# 12V_PowerSupply_V01.net
KiCad netlist of a schematic drawn in EAGLE
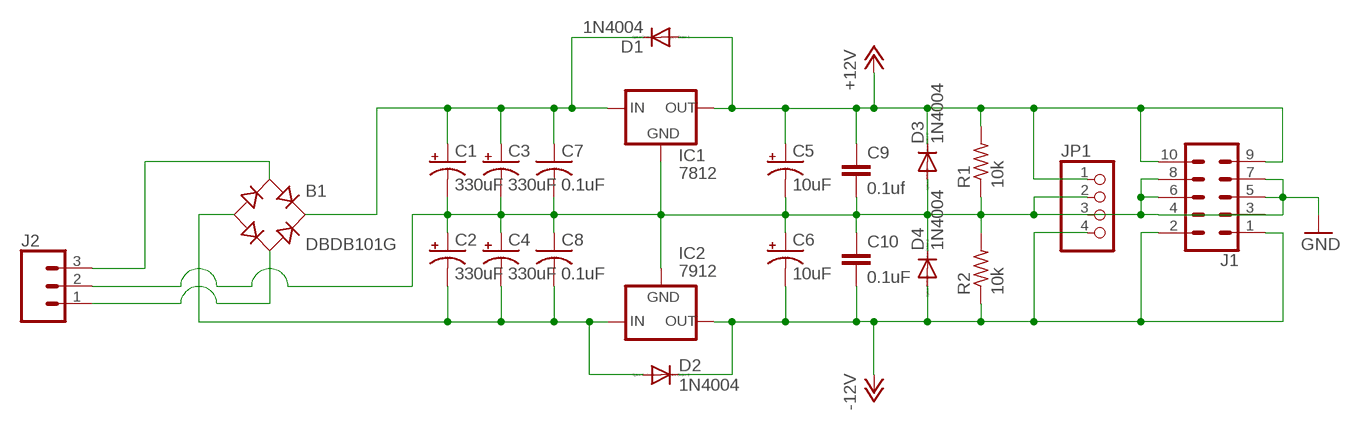
[diagram p0: schematic, sheet 1]

(export (version "E")
  (design (tool "Eeschema 10.0.6"))
  (components
    (comp (ref "B1")
      (value "DBDB101G")
      (footprint "eagle-import:DB")
      (libsource (lib "eagle-import") (part "DB?GDB101"))
    )
    (comp (ref "C1")
      (value "330uF")
      (footprint "eagle-import:E7,5-18")
      (libsource (lib "eagle-import") (part "CPOL-USE7.5-18"))
    )
    (comp (ref "C2")
      (value "330uF")
      (footprint "eagle-import:E7,5-18")
      (libsource (lib "eagle-import") (part "CPOL-USE7.5-18"))
    )
    (comp (ref "C3")
      (value "330uF")
      (footprint "eagle-import:E7,5-18")
      (libsource (lib "eagle-import") (part "CPOL-USE7.5-18"))
    )
    (comp (ref "C4")
      (value "330uF")
      (footprint "eagle-import:E7,5-18")
      (libsource (lib "eagle-import") (part "CPOL-USE7.5-18"))
    )
    (comp (ref "C5")
      (value "10uF")
      (footprint "eagle-import:E2,5-7")
      (libsource (lib "eagle-import") (part "CPOL-USE2.5-7"))
    )
    (comp (ref "C6")
      (value "10uF")
      (footprint "eagle-import:E2,5-7")
      (libsource (lib "eagle-import") (part "CPOL-USE2.5-7"))
    )
    (comp (ref "C7")
      (value "0.1uF")
      (footprint "eagle-import:C150-054X183")
      (libsource (lib "eagle-import") (part "C-US150-054X183"))
    )
    (comp (ref "C8")
      (value "0.1uF")
      (footprint "eagle-import:C150-054X183")
      (libsource (lib "eagle-import") (part "C-US150-054X183"))
    )
    (comp (ref "C9")
      (value "0.1uf")
      (footprint "eagle-import:C050-025X075")
      (libsource (lib "eagle-import") (part "C-EU050-025X075"))
    )
    (comp (ref "C10")
      (value "0.1uF")
      (footprint "eagle-import:C050-025X075")
      (libsource (lib "eagle-import") (part "C-EU050-025X075"))
    )
    (comp (ref "D1")
      (value "1N4004")
      (footprint "eagle-import:DO41-10")
      (libsource (lib "eagle-import") (part "1N4004"))
    )
    (comp (ref "D2")
      (value "1N4004")
      (footprint "eagle-import:DO41-10")
      (libsource (lib "eagle-import") (part "1N4004"))
    )
    (comp (ref "D3")
      (value "1N4004")
      (footprint "eagle-import:DO41-10")
      (libsource (lib "eagle-import") (part "1N4004"))
    )
    (comp (ref "D4")
      (value "1N4004")
      (footprint "eagle-import:DO41-10")
      (libsource (lib "eagle-import") (part "1N4004"))
    )
    (comp (ref "IC1")
      (value "7812")
      (footprint "eagle-import:78XXS")
      (libsource (lib "eagle-import") (part "78XXS"))
    )
    (comp (ref "IC2")
      (value "7912")
      (footprint "eagle-import:79XXS")
      (libsource (lib "eagle-import") (part "79XXS"))
    )
    (comp (ref "J1")
      (value "CONN_05X2SHD")
      (footprint "eagle-import:2X5-SHROUDED")
      (libsource (lib "eagle-import") (part "CONN_05X2SHD"))
    )
    (comp (ref "J2")
      (value "CONN_03-SCREW-5MM")
      (footprint "eagle-import:SCREWTERMINAL-5MM-3")
      (libsource (lib "eagle-import") (part "CONN_03-SCREW-5MM"))
    )
    (comp (ref "JP1")
      (value "PINHD-1X4")
      (footprint "eagle-import:1X04")
      (libsource (lib "eagle-import") (part "PINHD-1X4"))
    )
    (comp (ref "R1")
      (value "10k")
      (footprint "eagle-import:0204_7")
      (libsource (lib "eagle-import") (part "R-US_0204/7"))
    )
    (comp (ref "R2")
      (value "10k")
      (footprint "eagle-import:0204_7")
      (libsource (lib "eagle-import") (part "R-US_0204/7"))
    )
  )
  (nets
    (net (code "1") (name "+12V") (class "Default")
      (node (ref "C5") (pin "+") (pinfunction "+_+") (pintype "passive"))
      (node (ref "C9") (pin "1") (pinfunction "1_1") (pintype "passive"))
      (node (ref "D1") (pin "A") (pinfunction "A_A") (pintype "passive"))
      (node (ref "D3") (pin "C") (pinfunction "C_C") (pintype "passive"))
      (node (ref "IC1") (pin "OUT") (pinfunction "OUT_OUT") (pintype "passive"))
      (node (ref "J1") (pin "10") (pinfunction "10_10") (pintype "passive"))
      (node (ref "J1") (pin "9") (pinfunction "9_9") (pintype "passive"))
      (node (ref "JP1") (pin "1") (pinfunction "1_1") (pintype "passive"))
      (node (ref "R1") (pin "2") (pinfunction "2_2") (pintype "passive"))
    )
    (net (code "2") (name "-12V") (class "Default")
      (node (ref "C10") (pin "2") (pinfunction "2_2") (pintype "passive"))
      (node (ref "C6") (pin "-") (pinfunction "-_-") (pintype "passive"))
      (node (ref "D2") (pin "C") (pinfunction "C_C") (pintype "passive"))
      (node (ref "D4") (pin "A") (pinfunction "A_A") (pintype "passive"))
      (node (ref "IC2") (pin "OUT") (pinfunction "OUT_OUT") (pintype "passive"))
      (node (ref "J1") (pin "1") (pinfunction "1_1") (pintype "passive"))
      (node (ref "J1") (pin "2") (pinfunction "2_2") (pintype "passive"))
      (node (ref "JP1") (pin "4") (pinfunction "4_4") (pintype "passive"))
      (node (ref "R2") (pin "1") (pinfunction "1_1") (pintype "passive"))
    )
    (net (code "3") (name "GND") (class "Default")
      (node (ref "C1") (pin "-") (pinfunction "-_-") (pintype "passive"))
      (node (ref "C10") (pin "1") (pinfunction "1_1") (pintype "passive"))
      (node (ref "C2") (pin "+") (pinfunction "+_+") (pintype "passive"))
      (node (ref "C3") (pin "-") (pinfunction "-_-") (pintype "passive"))
      (node (ref "C4") (pin "+") (pinfunction "+_+") (pintype "passive"))
      (node (ref "C5") (pin "-") (pinfunction "-_-") (pintype "passive"))
      (node (ref "C6") (pin "+") (pinfunction "+_+") (pintype "passive"))
      (node (ref "C7") (pin "2") (pinfunction "2_2") (pintype "passive"))
      (node (ref "C8") (pin "1") (pinfunction "1_1") (pintype "passive"))
      (node (ref "C9") (pin "2") (pinfunction "2_2") (pintype "passive"))
      (node (ref "D3") (pin "A") (pinfunction "A_A") (pintype "passive"))
      (node (ref "D4") (pin "C") (pinfunction "C_C") (pintype "passive"))
      (node (ref "IC1") (pin "GND") (pinfunction "GND_GND") (pintype "input"))
      (node (ref "IC2") (pin "GND") (pinfunction "GND_GND") (pintype "input"))
      (node (ref "J1") (pin "3") (pinfunction "3_3") (pintype "passive"))
      (node (ref "J1") (pin "4") (pinfunction "4_4") (pintype "passive"))
      (node (ref "J1") (pin "5") (pinfunction "5_5") (pintype "passive"))
      (node (ref "J1") (pin "6") (pinfunction "6_6") (pintype "passive"))
      (node (ref "J1") (pin "7") (pinfunction "7_7") (pintype "passive"))
      (node (ref "J1") (pin "8") (pinfunction "8_8") (pintype "passive"))
      (node (ref "J2") (pin "2") (pinfunction "2_2") (pintype "passive"))
      (node (ref "JP1") (pin "2") (pinfunction "2_2") (pintype "passive"))
      (node (ref "JP1") (pin "3") (pinfunction "3_3") (pintype "passive"))
      (node (ref "R1") (pin "1") (pinfunction "1_1") (pintype "passive"))
      (node (ref "R2") (pin "2") (pinfunction "2_2") (pintype "passive"))
    )
    (net (code "4") (name "Net-(B1-Pad+)") (class "Default")
      (node (ref "B1") (pin "+") (pinfunction "+_+") (pintype "passive"))
      (node (ref "C1") (pin "+") (pinfunction "+_+") (pintype "passive"))
      (node (ref "C3") (pin "+") (pinfunction "+_+") (pintype "passive"))
      (node (ref "C7") (pin "1") (pinfunction "1_1") (pintype "passive"))
      (node (ref "D1") (pin "C") (pinfunction "C_C") (pintype "passive"))
      (node (ref "IC1") (pin "IN") (pinfunction "IN_IN") (pintype "input"))
    )
    (net (code "5") (name "Net-(B1-Pad-)") (class "Default")
      (node (ref "B1") (pin "-") (pinfunction "-_-") (pintype "passive"))
      (node (ref "C2") (pin "-") (pinfunction "-_-") (pintype "passive"))
      (node (ref "C4") (pin "-") (pinfunction "-_-") (pintype "passive"))
      (node (ref "C8") (pin "2") (pinfunction "2_2") (pintype "passive"))
      (node (ref "D2") (pin "A") (pinfunction "A_A") (pintype "passive"))
      (node (ref "IC2") (pin "IN") (pinfunction "IN_IN") (pintype "input"))
    )
    (net (code "6") (name "Net-(B1-PadAC1)") (class "Default")
      (node (ref "B1") (pin "AC1") (pinfunction "AC1_AC1") (pintype "passive"))
      (node (ref "J2") (pin "3") (pinfunction "3_3") (pintype "passive"))
    )
    (net (code "7") (name "Net-(B1-PadAC2)") (class "Default")
      (node (ref "B1") (pin "AC2") (pinfunction "AC2_AC2") (pintype "passive"))
      (node (ref "J2") (pin "1") (pinfunction "1_1") (pintype "passive"))
    )
  )
)
